# Teensy36AdapterBoard.net
KiCad netlist of a schematic drawn in Altium Designer
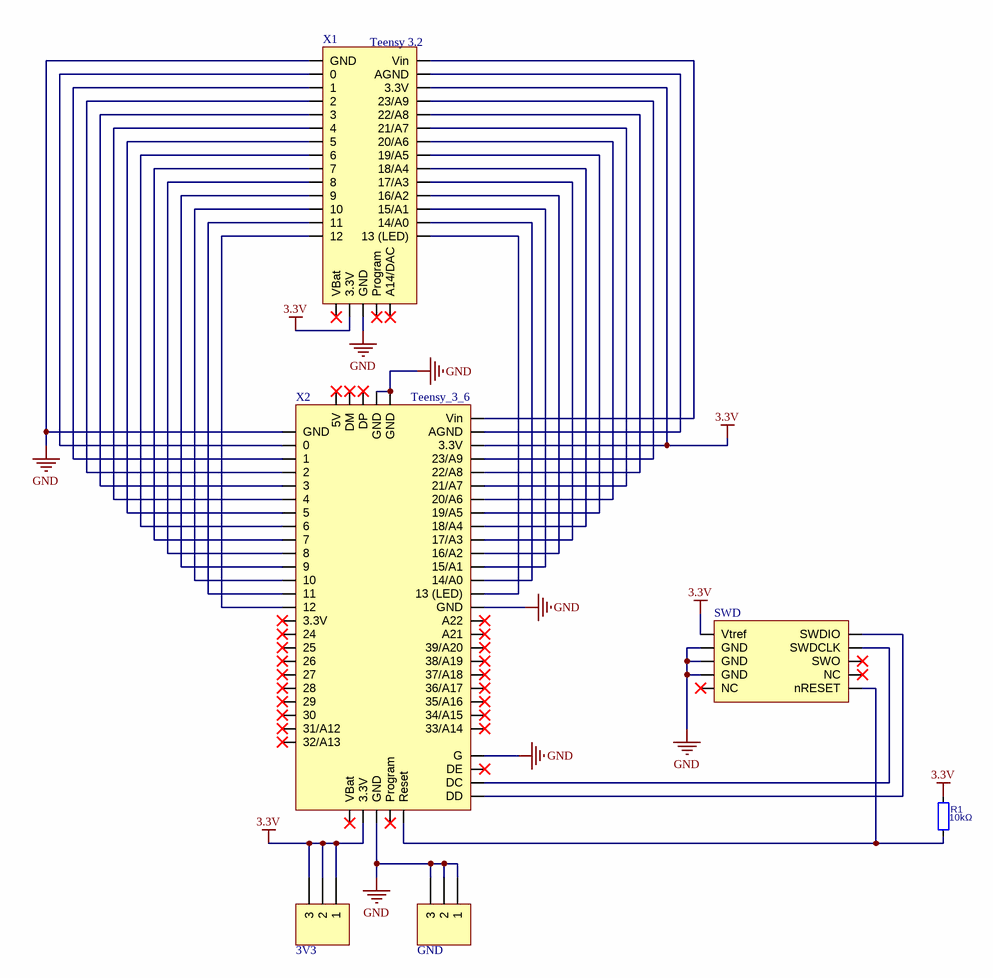
[diagram p0: Teensy36AdapterBoard.SchDoc]

(export (version "E")
  (design (tool "Eeschema 10.0.6"))
  (components
    (comp (ref "3V3")
      (value "3V3")
      (footprint "HDR1X3")
      (description "Header, 3-Pin")
      (fields (field (name "PUBLISHER") "Altium Limited"))
      (libsource (lib "Miscellaneous Connectors") (part "Header 3"))
    )
    (comp (ref "GND")
      (value "GND")
      (footprint "HDR1X3")
      (description "Header, 3-Pin")
      (fields (field (name "PUBLISHER") "Altium Limited"))
      (libsource (lib "Miscellaneous Connectors") (part "Header 3"))
    )
    (comp (ref "R1")
      (value "10kΩ")
      (footprint "0805")
      (description "Widerstand 0603")
      (fields (field (name "CHANGED BY") "taalbiss"))
      (libsource (lib "CCE_Database_Libs") (part "R_Normal"))
    )
    (comp (ref "SWD")
      (value "SWD_DebugInterface")
      (footprint "SWD Debug Interface 50mil")
      (libsource (lib "UAV") (part "SWD_DebugInterface"))
    )
    (comp (ref "X1")
      (value "Teensy 3.2")
      (footprint "UAV:Teensy_3_2")
      (libsource (lib "UAV") (part "Teensy_3_2"))
    )
    (comp (ref "X2") (value "Teensy_3_6") (libsource (lib "UAV") (part "Teensy_3_6")))
  )
  (nets
    (net (code "1") (name "3.3V") (class "Default")
      (node (ref "3V3") (pin "1") (pinfunction "1_1") (pintype "passive"))
      (node (ref "3V3") (pin "2") (pinfunction "2_2") (pintype "passive"))
      (node (ref "3V3") (pin "3") (pinfunction "3_3") (pintype "passive"))
      (node (ref "R1") (pin "2") (pinfunction "2_2") (pintype "passive"))
      (node (ref "SWD") (pin "1") (pinfunction "Vtref_1") (pintype "passive"))
      (node (ref "X1") (pin "3.3V_1") (pinfunction "3.3V_3.3V_1") (pintype "passive"))
      (node (ref "X1") (pin "3.3V_2") (pinfunction "3.3V_3.3V_2") (pintype "passive"))
      (node (ref "X2") (pin "3.3V_1") (pinfunction "3.3V_3.3V_1") (pintype "passive"))
      (node (ref "X2") (pin "3.3V_2") (pinfunction "3.3V_3.3V_2") (pintype "passive"))
    )
    (net (code "2") (name "GND") (class "Default")
      (node (ref "GND") (pin "1") (pinfunction "1_1") (pintype "passive"))
      (node (ref "GND") (pin "2") (pinfunction "2_2") (pintype "passive"))
      (node (ref "GND") (pin "3") (pinfunction "3_3") (pintype "passive"))
      (node (ref "SWD") (pin "5") (pinfunction "GND_5") (pintype "passive"))
      (node (ref "SWD") (pin "7") (pinfunction "GND_7") (pintype "passive"))
      (node (ref "SWD") (pin "9") (pinfunction "GND_9") (pintype "passive"))
      (node (ref "X1") (pin "GND_1") (pinfunction "GND_GND_1") (pintype "passive"))
      (node (ref "X1") (pin "GND_2") (pinfunction "GND_GND_2") (pintype "passive"))
      (node (ref "X2") (pin "GND_1") (pinfunction "GND_GND_1") (pintype "passive"))
      (node (ref "X2") (pin "GND_2") (pinfunction "GND_GND_2") (pintype "passive"))
      (node (ref "X2") (pin "GND_3") (pinfunction "GND_GND_3") (pintype "passive"))
      (node (ref "X2") (pin "GND_4") (pinfunction "G_GND_4") (pintype "passive"))
      (node (ref "X2") (pin "GND_5") (pinfunction "GND_GND_5") (pintype "passive"))
      (node (ref "X2") (pin "GND_6") (pinfunction "GND_GND_6") (pintype "passive"))
    )
    (net (code "3") (name "Net-(SWD-SWDCLK)") (class "Default")
      (node (ref "SWD") (pin "4") (pinfunction "SWDCLK_4") (pintype "passive"))
      (node (ref "X2") (pin "DC") (pinfunction "DC_DC") (pintype "passive"))
    )
    (net (code "4") (name "Net-(SWD-SWDIO)") (class "Default")
      (node (ref "SWD") (pin "2") (pinfunction "SWDIO_2") (pintype "passive"))
      (node (ref "X2") (pin "DD") (pinfunction "DD_DD") (pintype "passive"))
    )
    (net (code "5") (name "Net-(SWD-nRESET)") (class "Default")
      (node (ref "R1") (pin "1") (pinfunction "1_1") (pintype "passive"))
      (node (ref "SWD") (pin "10") (pinfunction "nRESET_10") (pintype "passive"))
      (node (ref "X2") (pin "Reset") (pinfunction "Reset_Reset") (pintype "passive"))
    )
    (net (code "6") (name "Net-(X1-13_(LED))") (class "Default")
      (node (ref "X1") (pin "13") (pinfunction "13_(LED)_13") (pintype "passive"))
      (node (ref "X2") (pin "13") (pinfunction "13_(LED)_13") (pintype "passive"))
    )
    (net (code "7") (name "Net-(X1-14{slash}A0)") (class "Default")
      (node (ref "X1") (pin "14") (pinfunction "14/A0_14") (pintype "passive"))
      (node (ref "X2") (pin "14") (pinfunction "14/A0_14") (pintype "passive"))
    )
    (net (code "8") (name "Net-(X1-15{slash}A1)") (class "Default")
      (node (ref "X1") (pin "15") (pinfunction "15/A1_15") (pintype "passive"))
      (node (ref "X2") (pin "15") (pinfunction "15/A1_15") (pintype "passive"))
    )
    (net (code "9") (name "Net-(X1-16{slash}A2)") (class "Default")
      (node (ref "X1") (pin "16") (pinfunction "16/A2_16") (pintype "passive"))
      (node (ref "X2") (pin "16") (pinfunction "16/A2_16") (pintype "passive"))
    )
    (net (code "10") (name "Net-(X1-17{slash}A3)") (class "Default")
      (node (ref "X1") (pin "17") (pinfunction "17/A3_17") (pintype "passive"))
      (node (ref "X2") (pin "17") (pinfunction "17/A3_17") (pintype "passive"))
    )
    (net (code "11") (name "Net-(X1-18{slash}A4)") (class "Default")
      (node (ref "X1") (pin "18") (pinfunction "18/A4_18") (pintype "passive"))
      (node (ref "X2") (pin "18") (pinfunction "18/A4_18") (pintype "passive"))
    )
    (net (code "12") (name "Net-(X1-19{slash}A5)") (class "Default")
      (node (ref "X1") (pin "19") (pinfunction "19/A5_19") (pintype "passive"))
      (node (ref "X2") (pin "19") (pinfunction "19/A5_19") (pintype "passive"))
    )
    (net (code "13") (name "Net-(X1-20{slash}A6)") (class "Default")
      (node (ref "X1") (pin "20") (pinfunction "20/A6_20") (pintype "passive"))
      (node (ref "X2") (pin "20") (pinfunction "20/A6_20") (pintype "passive"))
    )
    (net (code "14") (name "Net-(X1-21{slash}A7)") (class "Default")
      (node (ref "X1") (pin "21") (pinfunction "21/A7_21") (pintype "passive"))
      (node (ref "X2") (pin "21") (pinfunction "21/A7_21") (pintype "passive"))
    )
    (net (code "15") (name "Net-(X1-22{slash}A8)") (class "Default")
      (node (ref "X1") (pin "22") (pinfunction "22/A8_22") (pintype "passive"))
      (node (ref "X2") (pin "22") (pinfunction "22/A8_22") (pintype "passive"))
    )
    (net (code "16") (name "Net-(X1-23{slash}A9)") (class "Default")
      (node (ref "X1") (pin "23") (pinfunction "23/A9_23") (pintype "passive"))
      (node (ref "X2") (pin "23") (pinfunction "23/A9_23") (pintype "passive"))
    )
    (net (code "17") (name "Net-(X1-Pad0)") (class "Default")
      (node (ref "X1") (pin "0") (pinfunction "0_0") (pintype "passive"))
      (node (ref "X2") (pin "0") (pinfunction "0_0") (pintype "passive"))
    )
    (net (code "18") (name "Net-(X1-Pad1)") (class "Default")
      (node (ref "X1") (pin "1") (pinfunction "1_1") (pintype "passive"))
      (node (ref "X2") (pin "1") (pinfunction "1_1") (pintype "passive"))
    )
    (net (code "19") (name "Net-(X1-Pad2)") (class "Default")
      (node (ref "X1") (pin "2") (pinfunction "2_2") (pintype "passive"))
      (node (ref "X2") (pin "2") (pinfunction "2_2") (pintype "passive"))
    )
    (net (code "20") (name "Net-(X1-Pad3)") (class "Default")
      (node (ref "X1") (pin "3") (pinfunction "3_3") (pintype "passive"))
      (node (ref "X2") (pin "3") (pinfunction "3_3") (pintype "passive"))
    )
    (net (code "21") (name "Net-(X1-Pad4)") (class "Default")
      (node (ref "X1") (pin "4") (pinfunction "4_4") (pintype "passive"))
      (node (ref "X2") (pin "4") (pinfunction "4_4") (pintype "passive"))
    )
    (net (code "22") (name "Net-(X1-Pad5)") (class "Default")
      (node (ref "X1") (pin "5") (pinfunction "5_5") (pintype "passive"))
      (node (ref "X2") (pin "5") (pinfunction "5_5") (pintype "passive"))
    )
    (net (code "23") (name "Net-(X1-Pad6)") (class "Default")
      (node (ref "X1") (pin "6") (pinfunction "6_6") (pintype "passive"))
      (node (ref "X2") (pin "6") (pinfunction "6_6") (pintype "passive"))
    )
    (net (code "24") (name "Net-(X1-Pad7)") (class "Default")
      (node (ref "X1") (pin "7") (pinfunction "7_7") (pintype "passive"))
      (node (ref "X2") (pin "7") (pinfunction "7_7") (pintype "passive"))
    )
    (net (code "25") (name "Net-(X1-Pad8)") (class "Default")
      (node (ref "X1") (pin "8") (pinfunction "8_8") (pintype "passive"))
      (node (ref "X2") (pin "8") (pinfunction "8_8") (pintype "passive"))
    )
    (net (code "26") (name "Net-(X1-Pad9)") (class "Default")
      (node (ref "X1") (pin "9") (pinfunction "9_9") (pintype "passive"))
      (node (ref "X2") (pin "9") (pinfunction "9_9") (pintype "passive"))
    )
    (net (code "27") (name "Net-(X1-Pad10)") (class "Default")
      (node (ref "X1") (pin "10") (pinfunction "10_10") (pintype "passive"))
      (node (ref "X2") (pin "10") (pinfunction "10_10") (pintype "passive"))
    )
    (net (code "28") (name "Net-(X1-Pad11)") (class "Default")
      (node (ref "X1") (pin "11") (pinfunction "11_11") (pintype "passive"))
      (node (ref "X2") (pin "11") (pinfunction "11_11") (pintype "passive"))
    )
    (net (code "29") (name "Net-(X1-Pad12)") (class "Default")
      (node (ref "X1") (pin "12") (pinfunction "12_12") (pintype "passive"))
      (node (ref "X2") (pin "12") (pinfunction "12_12") (pintype "passive"))
    )
    (net (code "30") (name "Net-(X1-PadAGND)") (class "Default")
      (node (ref "X1") (pin "AGND") (pinfunction "AGND_AGND") (pintype "passive"))
      (node (ref "X2") (pin "AGND") (pinfunction "AGND_AGND") (pintype "passive"))
    )
    (net (code "31") (name "Net-(X1-PadVin)") (class "Default")
      (node (ref "X1") (pin "Vin") (pinfunction "Vin_Vin") (pintype "passive"))
      (node (ref "X2") (pin "Vin") (pinfunction "Vin_Vin") (pintype "passive"))
    )
    (net (code "32") (name "unconnected-(SWD-NC-Pad3)") (class "Default")
      (node (ref "SWD") (pin "3") (pinfunction "NC_3") (pintype "passive+no_connect"))
    )
    (net (code "33") (name "unconnected-(SWD-NC-Pad8)") (class "Default")
      (node (ref "SWD") (pin "8") (pinfunction "NC_8") (pintype "passive+no_connect"))
    )
    (net (code "34") (name "unconnected-(SWD-SWO-Pad6)") (class "Default")
      (node (ref "SWD") (pin "6") (pinfunction "SWO_6") (pintype "passive+no_connect"))
    )
    (net (code "35") (name "unconnected-(X1-A14{slash}DAC-PadA14)") (class "Default")
      (node (ref "X1") (pin "A14") (pinfunction "A14/DAC_A14") (pintype "passive+no_connect"))
    )
    (net (code "36") (name "unconnected-(X1-PadProgram)") (class "Default")
      (node (ref "X1") (pin "Program") (pinfunction "Program_Program") (pintype "passive+no_connect"))
    )
    (net (code "37") (name "unconnected-(X1-PadVBat)") (class "Default")
      (node (ref "X1") (pin "VBat") (pinfunction "VBat_VBat") (pintype "passive+no_connect"))
    )
    (net (code "38") (name "unconnected-(X2-5V-Pad5V_USB)") (class "Default")
      (node (ref "X2") (pin "5V_USB") (pinfunction "5V_5V_USB") (pintype "passive+no_connect"))
    )
    (net (code "39") (name "unconnected-(X2-31{slash}A12-Pad31)") (class "Default")
      (node (ref "X2") (pin "31") (pinfunction "31/A12_31") (pintype "passive+no_connect"))
    )
    (net (code "40") (name "unconnected-(X2-32{slash}A13-Pad32)") (class "Default")
      (node (ref "X2") (pin "32") (pinfunction "32/A13_32") (pintype "passive+no_connect"))
    )
    (net (code "41") (name "unconnected-(X2-33{slash}A14-Pad33)") (class "Default")
      (node (ref "X2") (pin "33") (pinfunction "33/A14_33") (pintype "passive+no_connect"))
    )
    (net (code "42") (name "unconnected-(X2-34{slash}A15-Pad34)") (class "Default")
      (node (ref "X2") (pin "34") (pinfunction "34/A15_34") (pintype "passive+no_connect"))
    )
    (net (code "43") (name "unconnected-(X2-35{slash}A16-Pad35)") (class "Default")
      (node (ref "X2") (pin "35") (pinfunction "35/A16_35") (pintype "passive+no_connect"))
    )
    (net (code "44") (name "unconnected-(X2-36{slash}A17-Pad36)") (class "Default")
      (node (ref "X2") (pin "36") (pinfunction "36/A17_36") (pintype "passive+no_connect"))
    )
    (net (code "45") (name "unconnected-(X2-37{slash}A18-Pad37)") (class "Default")
      (node (ref "X2") (pin "37") (pinfunction "37/A18_37") (pintype "passive+no_connect"))
    )
    (net (code "46") (name "unconnected-(X2-38{slash}A19-Pad38)") (class "Default")
      (node (ref "X2") (pin "38") (pinfunction "38/A19_38") (pintype "passive+no_connect"))
    )
    (net (code "47") (name "unconnected-(X2-39{slash}A20-Pad39)") (class "Default")
      (node (ref "X2") (pin "39") (pinfunction "39/A20_39") (pintype "passive+no_connect"))
    )
    (net (code "48") (name "unconnected-(X2-Pad3.3V)") (class "Default")
      (node (ref "X2") (pin "3.3V") (pinfunction "3.3V_3.3V") (pintype "passive+no_connect"))
    )
    (net (code "49") (name "unconnected-(X2-Pad24)") (class "Default")
      (node (ref "X2") (pin "24") (pinfunction "24_24") (pintype "passive+no_connect"))
    )
    (net (code "50") (name "unconnected-(X2-Pad25)") (class "Default")
      (node (ref "X2") (pin "25") (pinfunction "25_25") (pintype "passive+no_connect"))
    )
    (net (code "51") (name "unconnected-(X2-Pad26)") (class "Default")
      (node (ref "X2") (pin "26") (pinfunction "26_26") (pintype "passive+no_connect"))
    )
    (net (code "52") (name "unconnected-(X2-Pad27)") (class "Default")
      (node (ref "X2") (pin "27") (pinfunction "27_27") (pintype "passive+no_connect"))
    )
    (net (code "53") (name "unconnected-(X2-Pad28)") (class "Default")
      (node (ref "X2") (pin "28") (pinfunction "28_28") (pintype "passive+no_connect"))
    )
    (net (code "54") (name "unconnected-(X2-Pad29)") (class "Default")
      (node (ref "X2") (pin "29") (pinfunction "29_29") (pintype "passive+no_connect"))
    )
    (net (code "55") (name "unconnected-(X2-Pad30)") (class "Default")
      (node (ref "X2") (pin "30") (pinfunction "30_30") (pintype "passive+no_connect"))
    )
    (net (code "56") (name "unconnected-(X2-PadA21)") (class "Default")
      (node (ref "X2") (pin "A21") (pinfunction "A21_A21") (pintype "passive+no_connect"))
    )
    (net (code "57") (name "unconnected-(X2-PadA22)") (class "Default")
      (node (ref "X2") (pin "A22") (pinfunction "A22_A22") (pintype "passive+no_connect"))
    )
    (net (code "58") (name "unconnected-(X2-PadDE)") (class "Default")
      (node (ref "X2") (pin "DE") (pinfunction "DE_DE") (pintype "passive+no_connect"))
    )
    (net (code "59") (name "unconnected-(X2-PadDM)") (class "Default")
      (node (ref "X2") (pin "DM") (pinfunction "DM_DM") (pintype "passive+no_connect"))
    )
    (net (code "60") (name "unconnected-(X2-PadDP)") (class "Default")
      (node (ref "X2") (pin "DP") (pinfunction "DP_DP") (pintype "passive+no_connect"))
    )
    (net (code "61") (name "unconnected-(X2-PadProgram)") (class "Default")
      (node (ref "X2") (pin "Program") (pinfunction "Program_Program") (pintype "passive+no_connect"))
    )
    (net (code "62") (name "unconnected-(X2-PadVBat)") (class "Default")
      (node (ref "X2") (pin "VBat") (pinfunction "VBat_VBat") (pintype "passive+no_connect"))
    )
  )
)
